# Power_Supply_Adapter_Schematic.net
KiCad netlist of a schematic drawn in EasyEDA
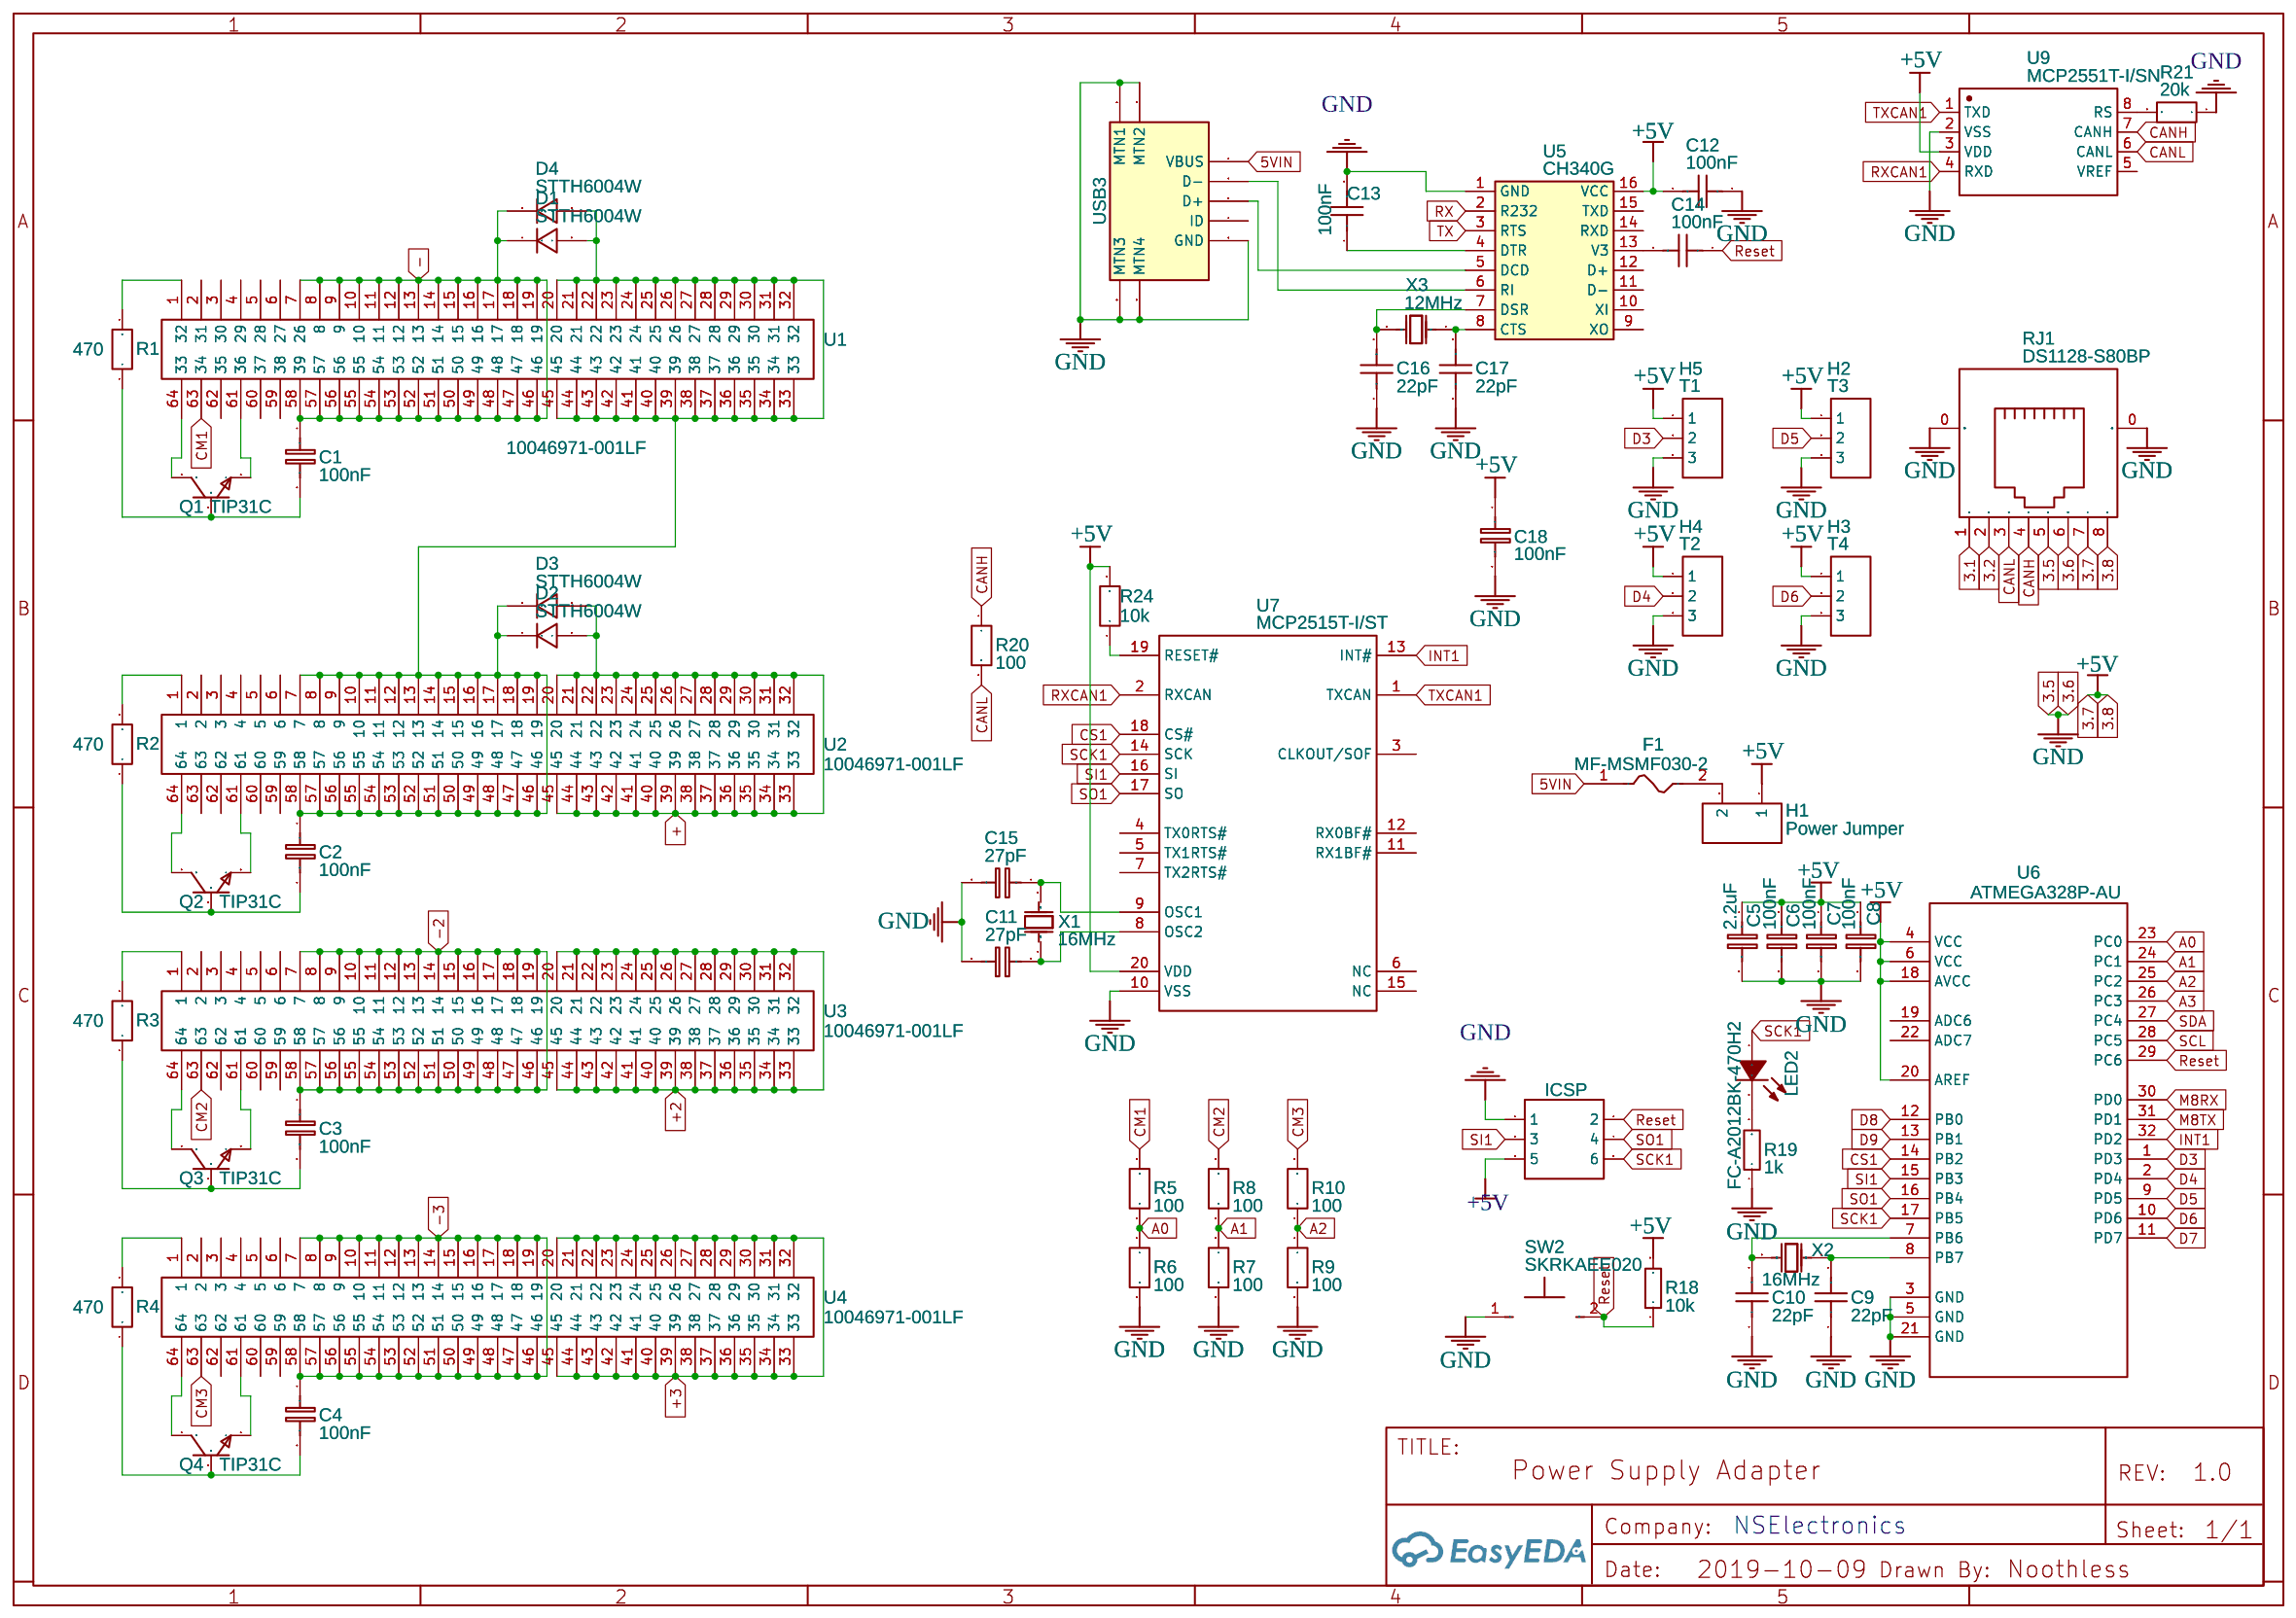
[diagram p0: schematic sheet]

(export (version "E")
  (design (tool "Eeschema 10.0.6"))
  (components
    (comp (ref "C1")
      (value "100nF")
      (fields
        (field (name "BOM_Manufacturer Part") "CL21B104KBCNNNC")
        (field (name "BOM_Supplier Part") "C1711")
      )
      (libsource (lib "") (part "Cap_0805_EU_2"))
    )
    (comp (ref "C2")
      (value "100nF")
      (fields
        (field (name "BOM_Manufacturer Part") "CL21B104KBCNNNC")
        (field (name "BOM_Supplier Part") "C1711")
      )
      (libsource (lib "") (part "Cap_0805_EU_2"))
    )
    (comp (ref "C3")
      (value "100nF")
      (fields
        (field (name "BOM_Manufacturer Part") "CL21B104KBCNNNC")
        (field (name "BOM_Supplier Part") "C1711")
      )
      (libsource (lib "") (part "Cap_0805_EU"))
    )
    (comp (ref "C4")
      (value "100nF")
      (fields
        (field (name "BOM_Manufacturer Part") "CL21B104KBCNNNC")
        (field (name "BOM_Supplier Part") "C1711")
      )
      (libsource (lib "") (part "Cap_0805_EU"))
    )
    (comp (ref "C5")
      (value "2.2uF")
      (fields
        (field (name "BOM_Manufacturer Part") "CL21B104KBCNNNC")
        (field (name "BOM_Supplier Part") "C1711")
      )
      (libsource (lib "") (part "Cap_1206_EU"))
    )
    (comp (ref "C6")
      (value "100nF")
      (fields
        (field (name "BOM_Manufacturer Part") "CL21B104KBCNNNC")
        (field (name "BOM_Supplier Part") "C1711")
      )
      (libsource (lib "") (part "Cap_1206_EU"))
    )
    (comp (ref "C7")
      (value "100nF")
      (fields
        (field (name "BOM_Manufacturer Part") "CL21B104KBCNNNC")
        (field (name "BOM_Supplier Part") "C1711")
      )
      (libsource (lib "") (part "Cap_1206_EU"))
    )
    (comp (ref "C8")
      (value "100nF")
      (fields
        (field (name "BOM_Manufacturer Part") "CL21B104KBCNNNC")
        (field (name "BOM_Supplier Part") "C1711")
      )
      (libsource (lib "") (part "Cap_1206_EU"))
    )
    (comp (ref "C9")
      (value "22pF")
      (fields
        (field (name "BOM_Manufacturer Part") "0805CG220J500NT")
        (field (name "BOM_Supplier Part") "C38143")
      )
      (libsource (lib "") (part "Cap_0805_US"))
    )
    (comp (ref "C10")
      (value "22pF")
      (fields
        (field (name "BOM_Manufacturer Part") "0805CG220J500NT")
        (field (name "BOM_Supplier Part") "C38143")
      )
      (libsource (lib "") (part "Cap_0805_US"))
    )
    (comp (ref "C11") (value "27pF") (libsource (lib "") (part "Cap_0805_EU_1")))
    (comp (ref "C12")
      (value "100nF")
      (fields
        (field (name "BOM_Manufacturer Part") "CL21B104KBCNNNC")
        (field (name "BOM_Supplier Part") "C1711")
      )
      (libsource (lib "") (part "Cap_0805_US_1"))
    )
    (comp (ref "C13")
      (value "100nF")
      (fields
        (field (name "BOM_Manufacturer Part") "CL21B104KBCNNNC")
        (field (name "BOM_Supplier Part") "C1711")
      )
      (libsource (lib "") (part "Cap_0805_US"))
    )
    (comp (ref "C14")
      (value "100nF")
      (fields (field (name "BOM_Manufacturer Part") "?"))
      (libsource (lib "") (part "Cap_0805_US_1"))
    )
    (comp (ref "C15") (value "27pF") (libsource (lib "") (part "Cap_0805_EU_1")))
    (comp (ref "C16")
      (value "22pF")
      (fields
        (field (name "BOM_Manufacturer Part") "0805CG220J500NT")
        (field (name "BOM_Supplier Part") "C38143")
      )
      (libsource (lib "") (part "Cap_0805_US"))
    )
    (comp (ref "C17")
      (value "22pF")
      (fields
        (field (name "BOM_Manufacturer Part") "0805CG220J500NT")
        (field (name "BOM_Supplier Part") "C38143")
      )
      (libsource (lib "") (part "Cap_0805_US"))
    )
    (comp (ref "C18") (value "100nF") (libsource (lib "") (part "Cap_0805_EU_3")))
    (comp (ref "D1")
      (value "STTH6004W")
      (fields (field (name "BOM_Supplier Part") "C169788"))
      (libsource (lib "") (part "Unknown_270_115"))
    )
    (comp (ref "D2")
      (value "STTH6004W")
      (fields (field (name "BOM_Supplier Part") "C169788"))
      (libsource (lib "") (part "Unknown_270_315"))
    )
    (comp (ref "D3")
      (value "STTH6004W")
      (fields (field (name "BOM_Supplier Part") "C169788"))
      (libsource (lib "") (part "Unknown_270_300"))
    )
    (comp (ref "D4")
      (value "STTH6004W")
      (fields (field (name "BOM_Supplier Part") "C169788"))
      (libsource (lib "") (part "Unknown_270_100"))
    )
    (comp (ref "F1")
      (value "MF-MSMF030-2")
      (fields (field (name "BOM_Supplier Part") "C12604"))
      (libsource (lib "") (part "Unknown_835_390"))
    )
    (comp (ref "H1")
      (value "Power Jumper")
      (fields (field (name "BOM_Manufacturer Part") "826629-2") (field (name "BOM_Supplier Part") "C86471"))
      (libsource (lib "") (part "Header-Male-2.54_1x2"))
    )
    (comp (ref "H2")
      (value "T3")
      (fields
        (field (name "BOM_Manufacturer Part") "Header2.54mm 1*3P")
        (field (name "BOM_Supplier Part") "C49257")
      )
      (libsource (lib "") (part "Header-Male-2.54_1x3"))
    )
    (comp (ref "H3")
      (value "T4")
      (fields
        (field (name "BOM_Manufacturer Part") "Header2.54mm 1*3P")
        (field (name "BOM_Supplier Part") "C49257")
      )
      (libsource (lib "") (part "Header-Male-2.54_1x3"))
    )
    (comp (ref "H4")
      (value "T2")
      (fields
        (field (name "BOM_Manufacturer Part") "Header2.54mm 1*3P")
        (field (name "BOM_Supplier Part") "C49257")
      )
      (libsource (lib "") (part "Header-Male-2.54_1x3"))
    )
    (comp (ref "H5")
      (value "T1")
      (fields
        (field (name "BOM_Manufacturer Part") "Header2.54mm 1*3P")
        (field (name "BOM_Supplier Part") "C49257")
      )
      (libsource (lib "") (part "Header-Male-2.54_1x3"))
    )
    (comp (ref "ICSP2")
      (value "ICSP")
      (fields
        (field (name "BOM_Manufacturer Part") "Header-Male-2.54_2x3")
        (field (name "BOM_Supplier Part") "C65114")
      )
      (libsource (lib "") (part "Unknown_785_570"))
    )
    (comp (ref "LED2")
      (value "FC-A2012BK-470H2")
      (fields (field (name "BOM_Supplier Part") "C84259"))
      (libsource (lib "") (part "Unknown_880_535"))
    )
    (comp (ref "Q1")
      (value "TIP31C")
      (fields (field (name "BOM_Supplier Part") "C13506"))
      (libsource (lib "") (part "Unknown_100_245"))
    )
    (comp (ref "Q2")
      (value "TIP31C")
      (fields (field (name "BOM_Supplier Part") "C13506"))
      (libsource (lib "") (part "Unknown_100_445"))
    )
    (comp (ref "Q3")
      (value "TIP31C")
      (fields (field (name "BOM_Supplier Part") "C13506"))
      (libsource (lib "") (part "Unknown_100_585"))
    )
    (comp (ref "Q4")
      (value "TIP31C")
      (fields (field (name "BOM_Supplier Part") "C13506"))
      (libsource (lib "") (part "Unknown_100_730"))
    )
    (comp (ref "R1")
      (value "470")
      (fields
        (field (name "BOM_Manufacturer Part") "0805W8J0471T5E")
        (field (name "BOM_Supplier Part") "C21266")
      )
      (libsource (lib "") (part "Res_0805(1/8W)_EU"))
    )
    (comp (ref "R2")
      (value "470")
      (fields
        (field (name "BOM_Manufacturer Part") "0805W8J0471T5E")
        (field (name "BOM_Supplier Part") "C21266")
      )
      (libsource (lib "") (part "Res_0805(1/8W)_EU"))
    )
    (comp (ref "R3")
      (value "470")
      (fields
        (field (name "BOM_Manufacturer Part") "0805W8J0471T5E")
        (field (name "BOM_Supplier Part") "C21266")
      )
      (libsource (lib "") (part "Res_0805(1/8W)_EU"))
    )
    (comp (ref "R4")
      (value "470")
      (fields
        (field (name "BOM_Manufacturer Part") "0805W8J0471T5E")
        (field (name "BOM_Supplier Part") "C21266")
      )
      (libsource (lib "") (part "Res_0805(1/8W)_EU"))
    )
    (comp (ref "R5") (value "100") (libsource (lib "") (part "Res_0805(1/8W)_EU")))
    (comp (ref "R6") (value "100") (libsource (lib "") (part "Res_0805(1/8W)_EU_1")))
    (comp (ref "R7") (value "100") (libsource (lib "") (part "Res_0805(1/8W)_EU_1")))
    (comp (ref "R8") (value "100") (libsource (lib "") (part "Res_0805(1/8W)_EU")))
    (comp (ref "R9") (value "100") (libsource (lib "") (part "Res_0805(1/8W)_EU_1")))
    (comp (ref "R10") (value "100") (libsource (lib "") (part "Res_0805(1/8W)_EU")))
    (comp (ref "R18")
      (value "10k")
      (fields
        (field (name "BOM_Manufacturer Part") "0805W8F1002T5E")
        (field (name "BOM_Supplier Part") "C17414")
      )
      (libsource (lib "") (part "Res_0805(1/8W)_EU_3"))
    )
    (comp (ref "R19")
      (value "1k")
      (fields
        (field (name "BOM_Manufacturer Part") "0805W8F1001T5E")
        (field (name "BOM_Supplier Part") "C17513")
      )
      (libsource (lib "") (part "Res_0805(1/8W)_EU_3"))
    )
    (comp (ref "R20") (value "100") (libsource (lib "") (part "Res_0805(1/8W)_EU_1")))
    (comp (ref "R21") (value "20k") (libsource (lib "") (part "Res_0805(1/8W)_EU_2")))
    (comp (ref "R24") (value "10k") (libsource (lib "") (part "Res_0805(1/8W)_EU")))
    (comp (ref "RJ1")
      (value "DS1128-S80BP")
      (fields (field (name "BOM_Supplier Part") "C86586"))
      (libsource (lib "") (part "Unknown_1025_225"))
    )
    (comp (ref "SW2")
      (value "SKRKAEE020")
      (fields (field (name "BOM_Supplier Part") "C115357"))
      (libsource (lib "") (part "Unknown_775_650"))
    )
    (comp (ref "U1")
      (value "10046971-001LF")
      (fields (field (name "BOM_Supplier Part") "609-2863-ND"))
      (libsource (lib "") (part "Unknown_75_185"))
    )
    (comp (ref "U2")
      (value "10046971-001LF")
      (fields (field (name "BOM_Supplier Part") "609-2863-ND"))
      (libsource (lib "") (part "Unknown_75_385"))
    )
    (comp (ref "U3")
      (value "10046971-001LF")
      (fields (field (name "BOM_Supplier Part") "609-2863-ND"))
      (libsource (lib "") (part "Unknown_75_525"))
    )
    (comp (ref "U4")
      (value "10046971-001LF")
      (fields (field (name "BOM_Supplier Part") "609-2863-ND"))
      (libsource (lib "") (part "Unknown_75_670"))
    )
    (comp (ref "U5")
      (value "CH340G")
      (fields (field (name "BOM_Supplier Part") "C14267"))
      (libsource (lib "") (part "Unknown_775_130"))
    )
    (comp (ref "U6")
      (value "ATMEGA328P-AU")
      (fields (field (name "BOM_Supplier Part") "C14877"))
      (libsource (lib "") (part "Unknown_1020_570"))
    )
    (comp (ref "U7")
      (value "MCP2515T-I/ST")
      (fields (field (name "BOM_Supplier Part") "C185941"))
      (libsource (lib "") (part "MCP2515T-I/ST"))
    )
    (comp (ref "U9")
      (value "MCP2551T-I/SN")
      (fields (field (name "BOM_Supplier Part") "C49558"))
      (libsource (lib "") (part "Unknown_1025_65"))
    )
    (comp (ref "USB3")
      (value "MINI 5PMotherboard Copper shell with column LCPVinyl")
      (fields (field (name "BOM_Supplier Part") "C46391"))
      (libsource (lib "") (part "Unknown_590_95"))
    )
    (comp (ref "X1")
      (value "16MHz")
      (fields
        (field (name "BOM_Manufacturer Part") "X49SD16MSD2SC")
        (field (name "BOM_Supplier Part") "C16212")
      )
      (libsource (lib "") (part "X49SD16MSD2SC_1"))
    )
    (comp (ref "X2")
      (value "16MHz")
      (fields
        (field (name "BOM_Manufacturer Part") "X49SD16MSD2SC")
        (field (name "BOM_Supplier Part") "C16212")
      )
      (libsource (lib "") (part "X49SD16MSD2SC"))
    )
    (comp (ref "X3")
      (value "12MHz")
      (fields
        (field (name "BOM_Manufacturer Part") "X49SD12MSD2SC")
        (field (name "BOM_Supplier Part") "C16369")
      )
      (libsource (lib "") (part "X49SD12MSD2SC"))
    )
  )
  (nets
    (net (code "1") (name "+") (class "Default")
      (node (ref "D2") (pin "2") (pinfunction "A_2") (pintype "unspecified"))
      (node (ref "D3") (pin "2") (pinfunction "A_2") (pintype "unspecified"))
      (node (ref "U2") (pin "20") (pinfunction "20_20") (pintype "unspecified"))
      (node (ref "U2") (pin "21") (pinfunction "21_21") (pintype "unspecified"))
      (node (ref "U2") (pin "22") (pinfunction "22_22") (pintype "unspecified"))
      (node (ref "U2") (pin "23") (pinfunction "23_23") (pintype "unspecified"))
      (node (ref "U2") (pin "24") (pinfunction "24_24") (pintype "unspecified"))
      (node (ref "U2") (pin "25") (pinfunction "25_25") (pintype "unspecified"))
      (node (ref "U2") (pin "26") (pinfunction "26_26") (pintype "unspecified"))
      (node (ref "U2") (pin "27") (pinfunction "27_27") (pintype "unspecified"))
      (node (ref "U2") (pin "28") (pinfunction "28_28") (pintype "unspecified"))
      (node (ref "U2") (pin "29") (pinfunction "29_29") (pintype "unspecified"))
      (node (ref "U2") (pin "30") (pinfunction "30_30") (pintype "unspecified"))
      (node (ref "U2") (pin "31") (pinfunction "31_31") (pintype "unspecified"))
      (node (ref "U2") (pin "32") (pinfunction "32_32") (pintype "unspecified"))
      (node (ref "U2") (pin "33") (pinfunction "33_33") (pintype "unspecified"))
      (node (ref "U2") (pin "34") (pinfunction "34_34") (pintype "unspecified"))
      (node (ref "U2") (pin "35") (pinfunction "35_35") (pintype "unspecified"))
      (node (ref "U2") (pin "36") (pinfunction "36_36") (pintype "unspecified"))
      (node (ref "U2") (pin "37") (pinfunction "37_37") (pintype "unspecified"))
      (node (ref "U2") (pin "38") (pinfunction "38_38") (pintype "unspecified"))
      (node (ref "U2") (pin "39") (pinfunction "39_39") (pintype "unspecified"))
      (node (ref "U2") (pin "40") (pinfunction "40_40") (pintype "unspecified"))
      (node (ref "U2") (pin "41") (pinfunction "41_41") (pintype "unspecified"))
      (node (ref "U2") (pin "42") (pinfunction "42_42") (pintype "unspecified"))
      (node (ref "U2") (pin "43") (pinfunction "43_43") (pintype "unspecified"))
      (node (ref "U2") (pin "44") (pinfunction "44_44") (pintype "unspecified"))
      (node (ref "U2") (pin "45") (pinfunction "45_45") (pintype "unspecified"))
    )
    (net (code "2") (name "+2") (class "Default")
      (node (ref "U3") (pin "20") (pinfunction "20_20") (pintype "unspecified"))
      (node (ref "U3") (pin "21") (pinfunction "21_21") (pintype "unspecified"))
      (node (ref "U3") (pin "22") (pinfunction "22_22") (pintype "unspecified"))
      (node (ref "U3") (pin "23") (pinfunction "23_23") (pintype "unspecified"))
      (node (ref "U3") (pin "24") (pinfunction "24_24") (pintype "unspecified"))
      (node (ref "U3") (pin "25") (pinfunction "25_25") (pintype "unspecified"))
      (node (ref "U3") (pin "26") (pinfunction "26_26") (pintype "unspecified"))
      (node (ref "U3") (pin "27") (pinfunction "27_27") (pintype "unspecified"))
      (node (ref "U3") (pin "28") (pinfunction "28_28") (pintype "unspecified"))
      (node (ref "U3") (pin "29") (pinfunction "29_29") (pintype "unspecified"))
      (node (ref "U3") (pin "30") (pinfunction "30_30") (pintype "unspecified"))
      (node (ref "U3") (pin "31") (pinfunction "31_31") (pintype "unspecified"))
      (node (ref "U3") (pin "32") (pinfunction "32_32") (pintype "unspecified"))
      (node (ref "U3") (pin "33") (pinfunction "33_33") (pintype "unspecified"))
      (node (ref "U3") (pin "34") (pinfunction "34_34") (pintype "unspecified"))
      (node (ref "U3") (pin "35") (pinfunction "35_35") (pintype "unspecified"))
      (node (ref "U3") (pin "36") (pinfunction "36_36") (pintype "unspecified"))
      (node (ref "U3") (pin "37") (pinfunction "37_37") (pintype "unspecified"))
      (node (ref "U3") (pin "38") (pinfunction "38_38") (pintype "unspecified"))
      (node (ref "U3") (pin "39") (pinfunction "39_39") (pintype "unspecified"))
      (node (ref "U3") (pin "40") (pinfunction "40_40") (pintype "unspecified"))
      (node (ref "U3") (pin "41") (pinfunction "41_41") (pintype "unspecified"))
      (node (ref "U3") (pin "42") (pinfunction "42_42") (pintype "unspecified"))
      (node (ref "U3") (pin "43") (pinfunction "43_43") (pintype "unspecified"))
      (node (ref "U3") (pin "44") (pinfunction "44_44") (pintype "unspecified"))
      (node (ref "U3") (pin "45") (pinfunction "45_45") (pintype "unspecified"))
    )
    (net (code "3") (name "+3") (class "Default")
      (node (ref "U4") (pin "20") (pinfunction "20_20") (pintype "unspecified"))
      (node (ref "U4") (pin "21") (pinfunction "21_21") (pintype "unspecified"))
      (node (ref "U4") (pin "22") (pinfunction "22_22") (pintype "unspecified"))
      (node (ref "U4") (pin "23") (pinfunction "23_23") (pintype "unspecified"))
      (node (ref "U4") (pin "24") (pinfunction "24_24") (pintype "unspecified"))
      (node (ref "U4") (pin "25") (pinfunction "25_25") (pintype "unspecified"))
      (node (ref "U4") (pin "26") (pinfunction "26_26") (pintype "unspecified"))
      (node (ref "U4") (pin "27") (pinfunction "27_27") (pintype "unspecified"))
      (node (ref "U4") (pin "28") (pinfunction "28_28") (pintype "unspecified"))
      (node (ref "U4") (pin "29") (pinfunction "29_29") (pintype "unspecified"))
      (node (ref "U4") (pin "30") (pinfunction "30_30") (pintype "unspecified"))
      (node (ref "U4") (pin "31") (pinfunction "31_31") (pintype "unspecified"))
      (node (ref "U4") (pin "32") (pinfunction "32_32") (pintype "unspecified"))
      (node (ref "U4") (pin "33") (pinfunction "33_33") (pintype "unspecified"))
      (node (ref "U4") (pin "34") (pinfunction "34_34") (pintype "unspecified"))
      (node (ref "U4") (pin "35") (pinfunction "35_35") (pintype "unspecified"))
      (node (ref "U4") (pin "36") (pinfunction "36_36") (pintype "unspecified"))
      (node (ref "U4") (pin "37") (pinfunction "37_37") (pintype "unspecified"))
      (node (ref "U4") (pin "38") (pinfunction "38_38") (pintype "unspecified"))
      (node (ref "U4") (pin "39") (pinfunction "39_39") (pintype "unspecified"))
      (node (ref "U4") (pin "40") (pinfunction "40_40") (pintype "unspecified"))
      (node (ref "U4") (pin "41") (pinfunction "41_41") (pintype "unspecified"))
      (node (ref "U4") (pin "42") (pinfunction "42_42") (pintype "unspecified"))
      (node (ref "U4") (pin "43") (pinfunction "43_43") (pintype "unspecified"))
      (node (ref "U4") (pin "44") (pinfunction "44_44") (pintype "unspecified"))
      (node (ref "U4") (pin "45") (pinfunction "45_45") (pintype "unspecified"))
    )
    (net (code "4") (name "-") (class "Default")
      (node (ref "C1") (pin "1") (pinfunction "1_1") (pintype "unspecified"))
      (node (ref "D1") (pin "1") (pinfunction "K_1") (pintype "unspecified"))
      (node (ref "D4") (pin "1") (pinfunction "K_1") (pintype "unspecified"))
      (node (ref "U1") (pin "10") (pinfunction "10_10") (pintype "unspecified"))
      (node (ref "U1") (pin "11") (pinfunction "11_11") (pintype "unspecified"))
      (node (ref "U1") (pin "12") (pinfunction "12_12") (pintype "unspecified"))
      (node (ref "U1") (pin "13") (pinfunction "13_13") (pintype "unspecified"))
      (node (ref "U1") (pin "14") (pinfunction "14_14") (pintype "unspecified"))
      (node (ref "U1") (pin "15") (pinfunction "15_15") (pintype "unspecified"))
      (node (ref "U1") (pin "16") (pinfunction "16_16") (pintype "unspecified"))
      (node (ref "U1") (pin "17") (pinfunction "17_17") (pintype "unspecified"))
      (node (ref "U1") (pin "18") (pinfunction "18_18") (pintype "unspecified"))
      (node (ref "U1") (pin "19") (pinfunction "19_19") (pintype "unspecified"))
      (node (ref "U1") (pin "46") (pinfunction "46_46") (pintype "unspecified"))
      (node (ref "U1") (pin "47") (pinfunction "47_47") (pintype "unspecified"))
      (node (ref "U1") (pin "48") (pinfunction "48_48") (pintype "unspecified"))
      (node (ref "U1") (pin "49") (pinfunction "49_49") (pintype "unspecified"))
      (node (ref "U1") (pin "50") (pinfunction "50_50") (pintype "unspecified"))
      (node (ref "U1") (pin "51") (pinfunction "51_51") (pintype "unspecified"))
      (node (ref "U1") (pin "52") (pinfunction "52_52") (pintype "unspecified"))
      (node (ref "U1") (pin "53") (pinfunction "53_53") (pintype "unspecified"))
      (node (ref "U1") (pin "54") (pinfunction "54_54") (pintype "unspecified"))
      (node (ref "U1") (pin "55") (pinfunction "55_55") (pintype "unspecified"))
      (node (ref "U1") (pin "56") (pinfunction "56_56") (pintype "unspecified"))
      (node (ref "U1") (pin "57") (pinfunction "57_57") (pintype "unspecified"))
      (node (ref "U1") (pin "58") (pinfunction "39_58") (pintype "unspecified"))
      (node (ref "U1") (pin "7") (pinfunction "26_7") (pintype "unspecified"))
      (node (ref "U1") (pin "8") (pinfunction "8_8") (pintype "unspecified"))
      (node (ref "U1") (pin "9") (pinfunction "9_9") (pintype "unspecified"))
    )
    (net (code "5") (name "-2") (class "Default")
      (node (ref "C3") (pin "1") (pinfunction "1_1") (pintype "unspecified"))
      (node (ref "U3") (pin "10") (pinfunction "10_10") (pintype "unspecified"))
      (node (ref "U3") (pin "11") (pinfunction "11_11") (pintype "unspecified"))
      (node (ref "U3") (pin "12") (pinfunction "12_12") (pintype "unspecified"))
      (node (ref "U3") (pin "13") (pinfunction "13_13") (pintype "unspecified"))
      (node (ref "U3") (pin "14") (pinfunction "14_14") (pintype "unspecified"))
      (node (ref "U3") (pin "15") (pinfunction "15_15") (pintype "unspecified"))
      (node (ref "U3") (pin "16") (pinfunction "16_16") (pintype "unspecified"))
      (node (ref "U3") (pin "17") (pinfunction "17_17") (pintype "unspecified"))
      (node (ref "U3") (pin "18") (pinfunction "18_18") (pintype "unspecified"))
      (node (ref "U3") (pin "19") (pinfunction "19_19") (pintype "unspecified"))
      (node (ref "U3") (pin "46") (pinfunction "46_46") (pintype "unspecified"))
      (node (ref "U3") (pin "47") (pinfunction "47_47") (pintype "unspecified"))
      (node (ref "U3") (pin "48") (pinfunction "48_48") (pintype "unspecified"))
      (node (ref "U3") (pin "49") (pinfunction "49_49") (pintype "unspecified"))
      (node (ref "U3") (pin "50") (pinfunction "50_50") (pintype "unspecified"))
      (node (ref "U3") (pin "51") (pinfunction "51_51") (pintype "unspecified"))
      (node (ref "U3") (pin "52") (pinfunction "52_52") (pintype "unspecified"))
      (node (ref "U3") (pin "53") (pinfunction "53_53") (pintype "unspecified"))
      (node (ref "U3") (pin "54") (pinfunction "54_54") (pintype "unspecified"))
      (node (ref "U3") (pin "55") (pinfunction "55_55") (pintype "unspecified"))
      (node (ref "U3") (pin "56") (pinfunction "56_56") (pintype "unspecified"))
      (node (ref "U3") (pin "57") (pinfunction "57_57") (pintype "unspecified"))
      (node (ref "U3") (pin "58") (pinfunction "58_58") (pintype "unspecified"))
      (node (ref "U3") (pin "7") (pinfunction "7_7") (pintype "unspecified"))
      (node (ref "U3") (pin "8") (pinfunction "8_8") (pintype "unspecified"))
      (node (ref "U3") (pin "9") (pinfunction "9_9") (pintype "unspecified"))
    )
    (net (code "6") (name "-3") (class "Default")
      (node (ref "C4") (pin "1") (pinfunction "1_1") (pintype "unspecified"))
      (node (ref "U4") (pin "10") (pinfunction "10_10") (pintype "unspecified"))
      (node (ref "U4") (pin "11") (pinfunction "11_11") (pintype "unspecified"))
      (node (ref "U4") (pin "12") (pinfunction "12_12") (pintype "unspecified"))
      (node (ref "U4") (pin "13") (pinfunction "13_13") (pintype "unspecified"))
      (node (ref "U4") (pin "14") (pinfunction "14_14") (pintype "unspecified"))
      (node (ref "U4") (pin "15") (pinfunction "15_15") (pintype "unspecified"))
      (node (ref "U4") (pin "16") (pinfunction "16_16") (pintype "unspecified"))
      (node (ref "U4") (pin "17") (pinfunction "17_17") (pintype "unspecified"))
      (node (ref "U4") (pin "18") (pinfunction "18_18") (pintype "unspecified"))
      (node (ref "U4") (pin "19") (pinfunction "19_19") (pintype "unspecified"))
      (node (ref "U4") (pin "46") (pinfunction "46_46") (pintype "unspecified"))
      (node (ref "U4") (pin "47") (pinfunction "47_47") (pintype "unspecified"))
      (node (ref "U4") (pin "48") (pinfunction "48_48") (pintype "unspecified"))
      (node (ref "U4") (pin "49") (pinfunction "49_49") (pintype "unspecified"))
      (node (ref "U4") (pin "50") (pinfunction "50_50") (pintype "unspecified"))
      (node (ref "U4") (pin "51") (pinfunction "51_51") (pintype "unspecified"))
      (node (ref "U4") (pin "52") (pinfunction "52_52") (pintype "unspecified"))
      (node (ref "U4") (pin "53") (pinfunction "53_53") (pintype "unspecified"))
      (node (ref "U4") (pin "54") (pinfunction "54_54") (pintype "unspecified"))
      (node (ref "U4") (pin "55") (pinfunction "55_55") (pintype "unspecified"))
      (node (ref "U4") (pin "56") (pinfunction "56_56") (pintype "unspecified"))
      (node (ref "U4") (pin "57") (pinfunction "57_57") (pintype "unspecified"))
      (node (ref "U4") (pin "58") (pinfunction "58_58") (pintype "unspecified"))
      (node (ref "U4") (pin "7") (pinfunction "7_7") (pintype "unspecified"))
      (node (ref "U4") (pin "8") (pinfunction "8_8") (pintype "unspecified"))
      (node (ref "U4") (pin "9") (pinfunction "9_9") (pintype "unspecified"))
    )
    (net (code "7") (name "3.1") (class "Default")
      (node (ref "RJ1") (pin "1") (pinfunction "1_1") (pintype "unspecified"))
    )
    (net (code "8") (name "3.2") (class "Default")
      (node (ref "RJ1") (pin "2") (pinfunction "2_2") (pintype "unspecified"))
    )
    (net (code "9") (name "3.5") (class "Default")
      (node (ref "C10") (pin "1") (pinfunction "1_1") (pintype "unspecified"))
      (node (ref "C11") (pin "2") (pinfunction "2_2") (pintype "unspecified"))
      (node (ref "C12") (pin "1") (pinfunction "1_1") (pintype "unspecified"))
      (node (ref "C13") (pin "2") (pinfunction "2_2") (pintype "unspecified"))
      (node (ref "C15") (pin "2") (pinfunction "2_2") (pintype "unspecified"))
      (node (ref "C16") (pin "1") (pinfunction "1_1") (pintype "unspecified"))
      (node (ref "C17") (pin "1") (pinfunction "1_1") (pintype "unspecified"))
      (node (ref "C18") (pin "2") (pinfunction "2_2") (pintype "unspecified"))
      (node (ref "C5") (pin "2") (pinfunction "2_2") (pintype "unspecified"))
      (node (ref "C6") (pin "2") (pinfunction "2_2") (pintype "unspecified"))
      (node (ref "C7") (pin "2") (pinfunction "2_2") (pintype "unspecified"))
      (node (ref "C8") (pin "2") (pinfunction "2_2") (pintype "unspecified"))
      (node (ref "C9") (pin "1") (pinfunction "1_1") (pintype "unspecified"))
      (node (ref "H2") (pin "3") (pinfunction "3_3") (pintype "input"))
      (node (ref "H3") (pin "3") (pinfunction "3_3") (pintype "input"))
      (node (ref "H4") (pin "3") (pinfunction "3_3") (pintype "input"))
      (node (ref "H5") (pin "3") (pinfunction "3_3") (pintype "input"))
      (node (ref "ICSP2") (pin "1") (pinfunction "1_1") (pintype "input"))
      (node (ref "R19") (pin "1") (pinfunction "1_1") (pintype "unspecified"))
      (node (ref "R21") (pin "1") (pinfunction "1_1") (pintype "unspecified"))
      (node (ref "R6") (pin "2") (pinfunction "2_2") (pintype "unspecified"))
      (node (ref "R7") (pin "2") (pinfunction "2_2") (pintype "unspecified"))
      (node (ref "R9") (pin "2") (pinfunction "2_2") (pintype "unspecified"))
      (node (ref "RJ1") (pin "0") (pinfunction "SHIELD_0") (pintype "unspecified"))
      (node (ref "RJ1") (pin "5") (pinfunction "5_5") (pintype "unspecified"))
      (node (ref "RJ1") (pin "6") (pinfunction "6_6") (pintype "unspecified"))
      (node (ref "SW2") (pin "1") (pinfunction "1_1") (pintype "input"))
      (node (ref "U5") (pin "1") (pinfunction "GND_1") (pintype "unspecified"))
      (node (ref "U6") (pin "21") (pinfunction "GND_21") (pintype "unspecified"))
      (node (ref "U6") (pin "3") (pinfunction "GND_3") (pintype "unspecified"))
      (node (ref "U6") (pin "5") (pinfunction "GND_5") (pintype "unspecified"))
      (node (ref "U7") (pin "10") (pinfunction "VSS_10") (pintype "passive"))
      (node (ref "U9") (pin "2") (pinfunction "VSS_2") (pintype "unspecified"))
      (node (ref "USB3") (pin "0") (pinfunction "MTN4_0") (pintype "input"))
      (node (ref "USB3") (pin "5") (pinfunction "GND_5") (pintype "input"))
    )
    (net (code "10") (name "3.7") (class "Default")
      (node (ref "C12") (pin "2") (pinfunction "2_2") (pintype "unspecified"))
      (node (ref "C18") (pin "1") (pinfunction "1_1") (pintype "unspecified"))
      (node (ref "C5") (pin "1") (pinfunction "1_1") (pintype "unspecified"))
      (node (ref "C6") (pin "1") (pinfunction "1_1") (pintype "unspecified"))
      (node (ref "C7") (pin "1") (pinfunction "1_1") (pintype "unspecified"))
      (node (ref "C8") (pin "1") (pinfunction "1_1") (pintype "unspecified"))
      (node (ref "H1") (pin "1") (pinfunction "1_1") (pintype "unspecified"))
      (node (ref "H2") (pin "1") (pinfunction "1_1") (pintype "input"))
      (node (ref "H3") (pin "1") (pinfunction "1_1") (pintype "input"))
      (node (ref "H4") (pin "1") (pinfunction "1_1") (pintype "input"))
      (node (ref "H5") (pin "1") (pinfunction "1_1") (pintype "input"))
      (node (ref "ICSP2") (pin "5") (pinfunction "5_5") (pintype "input"))
      (node (ref "R18") (pin "2") (pinfunction "2_2") (pintype "unspecified"))
      (node (ref "R24") (pin "2") (pinfunction "2_2") (pintype "unspecified"))
      (node (ref "RJ1") (pin "7") (pinfunction "7_7") (pintype "unspecified"))
      (node (ref "RJ1") (pin "8") (pinfunction "8_8") (pintype "unspecified"))
      (node (ref "U5") (pin "16") (pinfunction "VCC_16") (pintype "unspecified"))
      (node (ref "U6") (pin "18") (pinfunction "AVCC_18") (pintype "passive"))
      (node (ref "U6") (pin "20") (pinfunction "AREF_20") (pintype "input"))
      (node (ref "U6") (pin "4") (pinfunction "VCC_4") (pintype "passive"))
      (node (ref "U6") (pin "6") (pinfunction "VCC_6") (pintype "passive"))
      (node (ref "U7") (pin "20") (pinfunction "VDD_20") (pintype "passive"))
      (node (ref "U9") (pin "3") (pinfunction "VDD_3") (pintype "unspecified"))
    )
    (net (code "11") (name "5VIN") (class "Default")
      (node (ref "F1") (pin "1") (pinfunction "1_1") (pintype "unspecified"))
      (node (ref "USB3") (pin "1") (pinfunction "VBUS_1") (pintype "input"))
    )
    (net (code "12") (name "A0") (class "Default")
      (node (ref "R5") (pin "1") (pinfunction "1_1") (pintype "unspecified"))
      (node (ref "R6") (pin "1") (pinfunction "1_1") (pintype "unspecified"))
      (node (ref "U6") (pin "23") (pinfunction "PC0_23") (pintype "unspecified"))
    )
    (net (code "13") (name "A1") (class "Default")
      (node (ref "R7") (pin "1") (pinfunction "1_1") (pintype "unspecified"))
      (node (ref "R8") (pin "1") (pinfunction "1_1") (pintype "unspecified"))
      (node (ref "U6") (pin "24") (pinfunction "PC1_24") (pintype "unspecified"))
    )
    (net (code "14") (name "A2") (class "Default")
      (node (ref "R10") (pin "1") (pinfunction "1_1") (pintype "unspecified"))
      (node (ref "R9") (pin "1") (pinfunction "1_1") (pintype "unspecified"))
      (node (ref "U6") (pin "25") (pinfunction "PC2_25") (pintype "unspecified"))
    )
    (net (code "15") (name "A3") (class "Default")
      (node (ref "U6") (pin "26") (pinfunction "PC3_26") (pintype "unspecified"))
    )
    (net (code "16") (name "CANH") (class "Default")
      (node (ref "R20") (pin "1") (pinfunction "1_1") (pintype "unspecified"))
      (node (ref "RJ1") (pin "4") (pinfunction "4_4") (pintype "unspecified"))
      (node (ref "U9") (pin "7") (pinfunction "CANH_7") (pintype "unspecified"))
    )
    (net (code "17") (name "CANL") (class "Default")
      (node (ref "R20") (pin "2") (pinfunction "2_2") (pintype "unspecified"))
      (node (ref "RJ1") (pin "3") (pinfunction "3_3") (pintype "unspecified"))
      (node (ref "U9") (pin "6") (pinfunction "CANL_6") (pintype "unspecified"))
    )
    (net (code "18") (name "CM1") (class "Default")
      (node (ref "R5") (pin "2") (pinfunction "2_2") (pintype "unspecified"))
      (node (ref "U1") (pin "63") (pinfunction "34_63") (pintype "unspecified"))
    )
    (net (code "19") (name "CM2") (class "Default")
      (node (ref "R8") (pin "2") (pinfunction "2_2") (pintype "unspecified"))
      (node (ref "U3") (pin "63") (pinfunction "63_63") (pintype "unspecified"))
    )
    (net (code "20") (name "CM3") (class "Default")
      (node (ref "R10") (pin "2") (pinfunction "2_2") (pintype "unspecified"))
      (node (ref "U4") (pin "63") (pinfunction "63_63") (pintype "unspecified"))
    )
    (net (code "21") (name "CS1") (class "Default")
      (node (ref "U6") (pin "14") (pinfunction "PB2_14") (pintype "unspecified"))
      (node (ref "U7") (pin "18") (pinfunction "CS#_18") (pintype "unspecified"))
    )
    (net (code "22") (name "D3") (class "Default")
      (node (ref "H5") (pin "2") (pinfunction "2_2") (pintype "input"))
      (node (ref "U6") (pin "1") (pinfunction "PD3_1") (pintype "unspecified"))
    )
    (net (code "23") (name "D4") (class "Default")
      (node (ref "H4") (pin "2") (pinfunction "2_2") (pintype "input"))
      (node (ref "U6") (pin "2") (pinfunction "PD4_2") (pintype "unspecified"))
    )
    (net (code "24") (name "D5") (class "Default")
      (node (ref "H2") (pin "2") (pinfunction "2_2") (pintype "input"))
      (node (ref "U6") (pin "9") (pinfunction "PD5_9") (pintype "unspecified"))
    )
    (net (code "25") (name "D6") (class "Default")
      (node (ref "H3") (pin "2") (pinfunction "2_2") (pintype "input"))
      (node (ref "U6") (pin "10") (pinfunction "PD6_10") (pintype "unspecified"))
    )
    (net (code "26") (name "D7") (class "Default")
      (node (ref "U6") (pin "11") (pinfunction "PD7_11") (pintype "unspecified"))
    )
    (net (code "27") (name "D8") (class "Default")
      (node (ref "U6") (pin "12") (pinfunction "PB0_12") (pintype "unspecified"))
    )
    (net (code "28") (name "D9") (class "Default")
      (node (ref "U6") (pin "13") (pinfunction "PB1_13") (pintype "unspecified"))
    )
    (net (code "29") (name "INT1") (class "Default")
      (node (ref "U6") (pin "32") (pinfunction "PD2_32") (pintype "unspecified"))
      (node (ref "U7") (pin "13") (pinfunction "INT#_13") (pintype "output"))
    )
    (net (code "30") (name "M8RX") (class "Default")
      (node (ref "U6") (pin "30") (pinfunction "PD0_30") (pintype "unspecified"))
    )
    (net (code "31") (name "M8TX") (class "Default")
      (node (ref "U6") (pin "31") (pinfunction "PD1_31") (pintype "unspecified"))
    )
    (net (code "32") (name "Net-(D1-A)") (class "Default")
      (node (ref "C2") (pin "1") (pinfunction "1_1") (pintype "unspecified"))
      (node (ref "D1") (pin "2") (pinfunction "A_2") (pintype "unspecified"))
      (node (ref "D2") (pin "1") (pinfunction "K_1") (pintype "unspecified"))
      (node (ref "D3") (pin "1") (pinfunction "K_1") (pintype "unspecified"))
      (node (ref "D4") (pin "2") (pinfunction "A_2") (pintype "unspecified"))
      (node (ref "U1") (pin "20") (pinfunction "20_20") (pintype "unspecified"))
      (node (ref "U1") (pin "21") (pinfunction "21_21") (pintype "unspecified"))
      (node (ref "U1") (pin "22") (pinfunction "22_22") (pintype "unspecified"))
      (node (ref "U1") (pin "23") (pinfunction "23_23") (pintype "unspecified"))
      (node (ref "U1") (pin "24") (pinfunction "24_24") (pintype "unspecified"))
      (node (ref "U1") (pin "25") (pinfunction "25_25") (pintype "unspecified"))
      (node (ref "U1") (pin "26") (pinfunction "26_26") (pintype "unspecified"))
      (node (ref "U1") (pin "27") (pinfunction "27_27") (pintype "unspecified"))
      (node (ref "U1") (pin "28") (pinfunction "28_28") (pintype "unspecified"))
      (node (ref "U1") (pin "29") (pinfunction "29_29") (pintype "unspecified"))
      (node (ref "U1") (pin "30") (pinfunction "30_30") (pintype "unspecified"))
      (node (ref "U1") (pin "31") (pinfunction "31_31") (pintype "unspecified"))
      (node (ref "U1") (pin "32") (pinfunction "32_32") (pintype "unspecified"))
      (node (ref "U1") (pin "33") (pinfunction "33_33") (pintype "unspecified"))
      (node (ref "U1") (pin "34") (pinfunction "34_34") (pintype "unspecified"))
      (node (ref "U1") (pin "35") (pinfunction "35_35") (pintype "unspecified"))
      (node (ref "U1") (pin "36") (pinfunction "36_36") (pintype "unspecified"))
      (node (ref "U1") (pin "37") (pinfunction "37_37") (pintype "unspecified"))
      (node (ref "U1") (pin "38") (pinfunction "38_38") (pintype "unspecified"))
      (node (ref "U1") (pin "39") (pinfunction "39_39") (pintype "unspecified"))
      (node (ref "U1") (pin "40") (pinfunction "40_40") (pintype "unspecified"))
      (node (ref "U1") (pin "41") (pinfunction "41_41") (pintype "unspecified"))
      (node (ref "U1") (pin "42") (pinfunction "42_42") (pintype "unspecified"))
      (node (ref "U1") (pin "43") (pinfunction "43_43") (pintype "unspecified"))
      (node (ref "U1") (pin "44") (pinfunction "44_44") (pintype "unspecified"))
      (node (ref "U1") (pin "45") (pinfunction "45_45") (pintype "unspecified"))
      (node (ref "U2") (pin "10") (pinfunction "10_10") (pintype "unspecified"))
      (node (ref "U2") (pin "11") (pinfunction "11_11") (pintype "unspecified"))
      (node (ref "U2") (pin "12") (pinfunction "12_12") (pintype "unspecified"))
      (node (ref "U2") (pin "13") (pinfunction "13_13") (pintype "unspecified"))
      (node (ref "U2") (pin "14") (pinfunction "14_14") (pintype "unspecified"))
      (node (ref "U2") (pin "15") (pinfunction "15_15") (pintype "unspecified"))
      (node (ref "U2") (pin "16") (pinfunction "16_16") (pintype "unspecified"))
      (node (ref "U2") (pin "17") (pinfunction "17_17") (pintype "unspecified"))
      (node (ref "U2") (pin "18") (pinfunction "18_18") (pintype "unspecified"))
      (node (ref "U2") (pin "19") (pinfunction "19_19") (pintype "unspecified"))
      (node (ref "U2") (pin "46") (pinfunction "46_46") (pintype "unspecified"))
      (node (ref "U2") (pin "47") (pinfunction "47_47") (pintype "unspecified"))
      (node (ref "U2") (pin "48") (pinfunction "48_48") (pintype "unspecified"))
      (node (ref "U2") (pin "49") (pinfunction "49_49") (pintype "unspecified"))
      (node (ref "U2") (pin "50") (pinfunction "50_50") (pintype "unspecified"))
      (node (ref "U2") (pin "51") (pinfunction "51_51") (pintype "unspecified"))
      (node (ref "U2") (pin "52") (pinfunction "52_52") (pintype "unspecified"))
      (node (ref "U2") (pin "53") (pinfunction "53_53") (pintype "unspecified"))
      (node (ref "U2") (pin "54") (pinfunction "54_54") (pintype "unspecified"))
      (node (ref "U2") (pin "55") (pinfunction "55_55") (pintype "unspecified"))
      (node (ref "U2") (pin "56") (pinfunction "56_56") (pintype "unspecified"))
      (node (ref "U2") (pin "57") (pinfunction "57_57") (pintype "unspecified"))
      (node (ref "U2") (pin "58") (pinfunction "58_58") (pintype "unspecified"))
      (node (ref "U2") (pin "7") (pinfunction "7_7") (pintype "unspecified"))
      (node (ref "U2") (pin "8") (pinfunction "8_8") (pintype "unspecified"))
      (node (ref "U2") (pin "9") (pinfunction "9_9") (pintype "unspecified"))
    )
    (net (code "33") (name "Net-(F1-Pad2)") (class "Default")
      (node (ref "F1") (pin "2") (pinfunction "2_2") (pintype "unspecified"))
      (node (ref "H1") (pin "2") (pinfunction "2_2") (pintype "unspecified"))
    )
    (net (code "34") (name "Net-(LED2-K)") (class "Default")
      (node (ref "LED2") (pin "2") (pinfunction "K_2") (pintype "unspecified"))
      (node (ref "R19") (pin "2") (pinfunction "2_2") (pintype "unspecified"))
    )
    (net (code "35") (name "Net-(Q1-B)") (class "Default")
      (node (ref "C1") (pin "2") (pinfunction "2_2") (pintype "unspecified"))
      (node (ref "Q1") (pin "1") (pinfunction "B_1") (pintype "unspecified"))
      (node (ref "R1") (pin "1") (pinfunction "1_1") (pintype "unspecified"))
    )
    (net (code "36") (name "Net-(Q1-C)") (class "Default")
      (node (ref "Q1") (pin "2") (pinfunction "C_2") (pintype "unspecified"))
      (node (ref "U1") (pin "64") (pinfunction "33_64") (pintype "unspecified"))
    )
    (net (code "37") (name "Net-(Q1-E)") (class "Default")
      (node (ref "Q1") (pin "3") (pinfunction "E_3") (pintype "unspecified"))
      (node (ref "U1") (pin "61") (pinfunction "36_61") (pintype "unspecified"))
    )
    (net (code "38") (name "Net-(Q2-B)") (class "Default")
      (node (ref "C2") (pin "2") (pinfunction "2_2") (pintype "unspecified"))
      (node (ref "Q2") (pin "1") (pinfunction "B_1") (pintype "unspecified"))
      (node (ref "R2") (pin "1") (pinfunction "1_1") (pintype "unspecified"))
    )
    (net (code "39") (name "Net-(Q2-C)") (class "Default")
      (node (ref "Q2") (pin "2") (pinfunction "C_2") (pintype "unspecified"))
      (node (ref "U2") (pin "64") (pinfunction "64_64") (pintype "unspecified"))
    )
    (net (code "40") (name "Net-(Q2-E)") (class "Default")
      (node (ref "Q2") (pin "3") (pinfunction "E_3") (pintype "unspecified"))
      (node (ref "U2") (pin "61") (pinfunction "61_61") (pintype "unspecified"))
    )
    (net (code "41") (name "Net-(Q3-B)") (class "Default")
      (node (ref "C3") (pin "2") (pinfunction "2_2") (pintype "unspecified"))
      (node (ref "Q3") (pin "1") (pinfunction "B_1") (pintype "unspecified"))
      (node (ref "R3") (pin "1") (pinfunction "1_1") (pintype "unspecified"))
    )
    (net (code "42") (name "Net-(Q3-C)") (class "Default")
      (node (ref "Q3") (pin "2") (pinfunction "C_2") (pintype "unspecified"))
      (node (ref "U3") (pin "64") (pinfunction "64_64") (pintype "unspecified"))
    )
    (net (code "43") (name "Net-(Q3-E)") (class "Default")
      (node (ref "Q3") (pin "3") (pinfunction "E_3") (pintype "unspecified"))
      (node (ref "U3") (pin "61") (pinfunction "61_61") (pintype "unspecified"))
    )
    (net (code "44") (name "Net-(Q4-B)") (class "Default")
      (node (ref "C4") (pin "2") (pinfunction "2_2") (pintype "unspecified"))
      (node (ref "Q4") (pin "1") (pinfunction "B_1") (pintype "unspecified"))
      (node (ref "R4") (pin "1") (pinfunction "1_1") (pintype "unspecified"))
    )
    (net (code "45") (name "Net-(Q4-C)") (class "Default")
      (node (ref "Q4") (pin "2") (pinfunction "C_2") (pintype "unspecified"))
      (node (ref "U4") (pin "64") (pinfunction "64_64") (pintype "unspecified"))
    )
    (net (code "46") (name "Net-(Q4-E)") (class "Default")
      (node (ref "Q4") (pin "3") (pinfunction "E_3") (pintype "unspecified"))
      (node (ref "U4") (pin "61") (pinfunction "61_61") (pintype "unspecified"))
    )
    (net (code "47") (name "Net-(R1-Pad2)") (class "Default")
      (node (ref "R1") (pin "2") (pinfunction "2_2") (pintype "unspecified"))
      (node (ref "U1") (pin "1") (pinfunction "32_1") (pintype "unspecified"))
    )
    (net (code "48") (name "Net-(R2-Pad2)") (class "Default")
      (node (ref "R2") (pin "2") (pinfunction "2_2") (pintype "unspecified"))
      (node (ref "U2") (pin "1") (pinfunction "1_1") (pintype "unspecified"))
    )
    (net (code "49") (name "Net-(R3-Pad2)") (class "Default")
      (node (ref "R3") (pin "2") (pinfunction "2_2") (pintype "unspecified"))
      (node (ref "U3") (pin "1") (pinfunction "1_1") (pintype "unspecified"))
    )
    (net (code "50") (name "Net-(R4-Pad2)") (class "Default")
      (node (ref "R4") (pin "2") (pinfunction "2_2") (pintype "unspecified"))
      (node (ref "U4") (pin "1") (pinfunction "1_1") (pintype "unspecified"))
    )
    (net (code "51") (name "Net-(U5-CTS)") (class "Default")
      (node (ref "C17") (pin "2") (pinfunction "2_2") (pintype "unspecified"))
      (node (ref "U5") (pin "8") (pinfunction "CTS_8") (pintype "unspecified"))
      (node (ref "X3") (pin "1") (pinfunction "OSC1_1") (pintype "input"))
    )
    (net (code "52") (name "Net-(U5-DCD)") (class "Default")
      (node (ref "U5") (pin "5") (pinfunction "DCD_5") (pintype "unspecified"))
      (node (ref "USB3") (pin "3") (pinfunction "D+_3") (pintype "input"))
    )
    (net (code "53") (name "Net-(U5-DSR)") (class "Default")
      (node (ref "C16") (pin "2") (pinfunction "2_2") (pintype "unspecified"))
      (node (ref "U5") (pin "7") (pinfunction "DSR_7") (pintype "unspecified"))
      (node (ref "X3") (pin "2") (pinfunction "OSC2_2") (pintype "input"))
    )
    (net (code "54") (name "Net-(U5-DTR)") (class "Default")
      (node (ref "C13") (pin "1") (pinfunction "1_1") (pintype "unspecified"))
      (node (ref "U5") (pin "4") (pinfunction "DTR_4") (pintype "unspecified"))
    )
    (net (code "55") (name "Net-(U5-RI)") (class "Default")
      (node (ref "U5") (pin "6") (pinfunction "RI_6") (pintype "unspecified"))
      (node (ref "USB3") (pin "2") (pinfunction "D-_2") (pintype "input"))
    )
    (net (code "56") (name "Net-(U5-V3)") (class "Default")
      (node (ref "C14") (pin "2") (pinfunction "2_2") (pintype "unspecified"))
      (node (ref "U5") (pin "13") (pinfunction "V3_13") (pintype "unspecified"))
    )
    (net (code "57") (name "Net-(U6-PB6)") (class "Default")
      (node (ref "C10") (pin "2") (pinfunction "2_2") (pintype "unspecified"))
      (node (ref "U6") (pin "7") (pinfunction "PB6_7") (pintype "unspecified"))
      (node (ref "X2") (pin "2") (pinfunction "OSC2_2") (pintype "input"))
    )
    (net (code "58") (name "Net-(U6-PB7)") (class "Default")
      (node (ref "C9") (pin "2") (pinfunction "2_2") (pintype "unspecified"))
      (node (ref "U6") (pin "8") (pinfunction "PB7_8") (pintype "unspecified"))
      (node (ref "X2") (pin "1") (pinfunction "OSC1_1") (pintype "input"))
    )
    (net (code "59") (name "Net-(U7-OSC1)") (class "Default")
      (node (ref "C15") (pin "1") (pinfunction "1_1") (pintype "unspecified"))
      (node (ref "U7") (pin "9") (pinfunction "OSC1_9") (pintype "unspecified"))
      (node (ref "X1") (pin "2") (pinfunction "OSC2_2") (pintype "input"))
    )
    (net (code "60") (name "Net-(U7-OSC2)") (class "Default")
      (node (ref "C11") (pin "1") (pinfunction "1_1") (pintype "unspecified"))
      (node (ref "U7") (pin "8") (pinfunction "OSC2_8") (pintype "output"))
      (node (ref "X1") (pin "1") (pinfunction "OSC1_1") (pintype "input"))
    )
    (net (code "61") (name "Net-(U7-RESET#)") (class "Default")
      (node (ref "R24") (pin "1") (pinfunction "1_1") (pintype "unspecified"))
      (node (ref "U7") (pin "19") (pinfunction "RESET#_19") (pintype "unspecified"))
    )
    (net (code "62") (name "Net-(U9-RS)") (class "Default")
      (node (ref "R21") (pin "2") (pinfunction "2_2") (pintype "unspecified"))
      (node (ref "U9") (pin "8") (pinfunction "RS_8") (pintype "unspecified"))
    )
    (net (code "63") (name "RX") (class "Default")
      (node (ref "U5") (pin "2") (pinfunction "R232_2") (pintype "unspecified"))
    )
    (net (code "64") (name "RXCAN1") (class "Default")
      (node (ref "U7") (pin "2") (pinfunction "RXCAN_2") (pintype "unspecified"))
      (node (ref "U9") (pin "4") (pinfunction "RXD_4") (pintype "unspecified"))
    )
    (net (code "65") (name "Reset") (class "Default")
      (node (ref "C14") (pin "1") (pinfunction "1_1") (pintype "unspecified"))
      (node (ref "ICSP2") (pin "2") (pinfunction "2_2") (pintype "input"))
      (node (ref "R18") (pin "1") (pinfunction "1_1") (pintype "unspecified"))
      (node (ref "SW2") (pin "2") (pinfunction "2_2") (pintype "input"))
      (node (ref "U6") (pin "29") (pinfunction "PC6_29") (pintype "unspecified"))
    )
    (net (code "66") (name "SCK1") (class "Default")
      (node (ref "ICSP2") (pin "6") (pinfunction "6_6") (pintype "input"))
      (node (ref "LED2") (pin "1") (pinfunction "A_1") (pintype "unspecified"))
      (node (ref "U6") (pin "17") (pinfunction "PB5_17") (pintype "unspecified"))
      (node (ref "U7") (pin "14") (pinfunction "SCK_14") (pintype "unspecified"))
    )
    (net (code "67") (name "SCL") (class "Default")
      (node (ref "U6") (pin "28") (pinfunction "PC5_28") (pintype "unspecified"))
    )
    (net (code "68") (name "SDA") (class "Default")
      (node (ref "U6") (pin "27") (pinfunction "PC4_27") (pintype "unspecified"))
    )
    (net (code "69") (name "SI1") (class "Default")
      (node (ref "ICSP2") (pin "3") (pinfunction "3_3") (pintype "input"))
      (node (ref "U6") (pin "15") (pinfunction "PB3_15") (pintype "unspecified"))
      (node (ref "U7") (pin "16") (pinfunction "SI_16") (pintype "unspecified"))
    )
    (net (code "70") (name "SO1") (class "Default")
      (node (ref "ICSP2") (pin "4") (pinfunction "4_4") (pintype "input"))
      (node (ref "U6") (pin "16") (pinfunction "PB4_16") (pintype "unspecified"))
      (node (ref "U7") (pin "17") (pinfunction "SO_17") (pintype "output"))
    )
    (net (code "71") (name "TX") (class "Default")
      (node (ref "U5") (pin "3") (pinfunction "RTS_3") (pintype "unspecified"))
    )
    (net (code "72") (name "TXCAN1") (class "Default")
      (node (ref "U7") (pin "1") (pinfunction "TXCAN_1") (pintype "output"))
      (node (ref "U9") (pin "1") (pinfunction "TXD_1") (pintype "unspecified"))
    )
    (net (code "73") (name "unconnected-(U1-27-Pad6)") (class "Default")
      (node (ref "U1") (pin "6") (pinfunction "27_6") (pintype "unspecified"))
    )
    (net (code "74") (name "unconnected-(U1-28-Pad5)") (class "Default")
      (node (ref "U1") (pin "5") (pinfunction "28_5") (pintype "unspecified"))
    )
    (net (code "75") (name "unconnected-(U1-29-Pad4)") (class "Default")
      (node (ref "U1") (pin "4") (pinfunction "29_4") (pintype "unspecified"))
    )
    (net (code "76") (name "unconnected-(U1-30-Pad3)") (class "Default")
      (node (ref "U1") (pin "3") (pinfunction "30_3") (pintype "unspecified"))
    )
    (net (code "77") (name "unconnected-(U1-31-Pad2)") (class "Default")
      (node (ref "U1") (pin "2") (pinfunction "31_2") (pintype "unspecified"))
    )
    (net (code "78") (name "unconnected-(U1-35-Pad62)") (class "Default")
      (node (ref "U1") (pin "62") (pinfunction "35_62") (pintype "unspecified"))
    )
    (net (code "79") (name "unconnected-(U1-37-Pad60)") (class "Default")
      (node (ref "U1") (pin "60") (pinfunction "37_60") (pintype "unspecified"))
    )
    (net (code "80") (name "unconnected-(U1-38-Pad59)") (class "Default")
      (node (ref "U1") (pin "59") (pinfunction "38_59") (pintype "unspecified"))
    )
    (net (code "81") (name "unconnected-(U2-Pad2)") (class "Default")
      (node (ref "U2") (pin "2") (pinfunction "2_2") (pintype "unspecified"))
    )
    (net (code "82") (name "unconnected-(U2-Pad3)") (class "Default")
      (node (ref "U2") (pin "3") (pinfunction "3_3") (pintype "unspecified"))
    )
    (net (code "83") (name "unconnected-(U2-Pad4)") (class "Default")
      (node (ref "U2") (pin "4") (pinfunction "4_4") (pintype "unspecified"))
    )
    (net (code "84") (name "unconnected-(U2-Pad5)") (class "Default")
      (node (ref "U2") (pin "5") (pinfunction "5_5") (pintype "unspecified"))
    )
    (net (code "85") (name "unconnected-(U2-Pad6)") (class "Default")
      (node (ref "U2") (pin "6") (pinfunction "6_6") (pintype "unspecified"))
    )
    (net (code "86") (name "unconnected-(U2-Pad59)") (class "Default")
      (node (ref "U2") (pin "59") (pinfunction "59_59") (pintype "unspecified"))
    )
    (net (code "87") (name "unconnected-(U2-Pad60)") (class "Default")
      (node (ref "U2") (pin "60") (pinfunction "60_60") (pintype "unspecified"))
    )
    (net (code "88") (name "unconnected-(U2-Pad62)") (class "Default")
      (node (ref "U2") (pin "62") (pinfunction "62_62") (pintype "unspecified"))
    )
    (net (code "89") (name "unconnected-(U2-Pad63)") (class "Default")
      (node (ref "U2") (pin "63") (pinfunction "63_63") (pintype "unspecified"))
    )
    (net (code "90") (name "unconnected-(U3-Pad2)") (class "Default")
      (node (ref "U3") (pin "2") (pinfunction "2_2") (pintype "unspecified"))
    )
    (net (code "91") (name "unconnected-(U3-Pad3)") (class "Default")
      (node (ref "U3") (pin "3") (pinfunction "3_3") (pintype "unspecified"))
    )
    (net (code "92") (name "unconnected-(U3-Pad4)") (class "Default")
      (node (ref "U3") (pin "4") (pinfunction "4_4") (pintype "unspecified"))
    )
    (net (code "93") (name "unconnected-(U3-Pad5)") (class "Default")
      (node (ref "U3") (pin "5") (pinfunction "5_5") (pintype "unspecified"))
    )
    (net (code "94") (name "unconnected-(U3-Pad6)") (class "Default")
      (node (ref "U3") (pin "6") (pinfunction "6_6") (pintype "unspecified"))
    )
    (net (code "95") (name "unconnected-(U3-Pad59)") (class "Default")
      (node (ref "U3") (pin "59") (pinfunction "59_59") (pintype "unspecified"))
    )
    (net (code "96") (name "unconnected-(U3-Pad60)") (class "Default")
      (node (ref "U3") (pin "60") (pinfunction "60_60") (pintype "unspecified"))
    )
    (net (code "97") (name "unconnected-(U3-Pad62)") (class "Default")
      (node (ref "U3") (pin "62") (pinfunction "62_62") (pintype "unspecified"))
    )
    (net (code "98") (name "unconnected-(U4-Pad2)") (class "Default")
      (node (ref "U4") (pin "2") (pinfunction "2_2") (pintype "unspecified"))
    )
    (net (code "99") (name "unconnected-(U4-Pad3)") (class "Default")
      (node (ref "U4") (pin "3") (pinfunction "3_3") (pintype "unspecified"))
    )
    (net (code "100") (name "unconnected-(U4-Pad4)") (class "Default")
      (node (ref "U4") (pin "4") (pinfunction "4_4") (pintype "unspecified"))
    )
    (net (code "101") (name "unconnected-(U4-Pad5)") (class "Default")
      (node (ref "U4") (pin "5") (pinfunction "5_5") (pintype "unspecified"))
    )
    (net (code "102") (name "unconnected-(U4-Pad6)") (class "Default")
      (node (ref "U4") (pin "6") (pinfunction "6_6") (pintype "unspecified"))
    )
    (net (code "103") (name "unconnected-(U4-Pad59)") (class "Default")
      (node (ref "U4") (pin "59") (pinfunction "59_59") (pintype "unspecified"))
    )
    (net (code "104") (name "unconnected-(U4-Pad60)") (class "Default")
      (node (ref "U4") (pin "60") (pinfunction "60_60") (pintype "unspecified"))
    )
    (net (code "105") (name "unconnected-(U4-Pad62)") (class "Default")
      (node (ref "U4") (pin "62") (pinfunction "62_62") (pintype "unspecified"))
    )
    (net (code "106") (name "unconnected-(U5-D+-Pad12)") (class "Default")
      (node (ref "U5") (pin "12") (pinfunction "D+_12") (pintype "unspecified"))
    )
    (net (code "107") (name "unconnected-(U5-D--Pad11)") (class "Default")
      (node (ref "U5") (pin "11") (pinfunction "D-_11") (pintype "unspecified"))
    )
    (net (code "108") (name "unconnected-(U5-RXD-Pad14)") (class "Default")
      (node (ref "U5") (pin "14") (pinfunction "RXD_14") (pintype "unspecified"))
    )
    (net (code "109") (name "unconnected-(U5-TXD-Pad15)") (class "Default")
      (node (ref "U5") (pin "15") (pinfunction "TXD_15") (pintype "unspecified"))
    )
    (net (code "110") (name "unconnected-(U5-XI-Pad10)") (class "Default")
      (node (ref "U5") (pin "10") (pinfunction "XI_10") (pintype "unspecified"))
    )
    (net (code "111") (name "unconnected-(U5-XO-Pad9)") (class "Default")
      (node (ref "U5") (pin "9") (pinfunction "XO_9") (pintype "unspecified"))
    )
    (net (code "112") (name "unconnected-(U6-ADC6-Pad19)") (class "Default")
      (node (ref "U6") (pin "19") (pinfunction "ADC6_19") (pintype "input"))
    )
    (net (code "113") (name "unconnected-(U6-ADC7-Pad22)") (class "Default")
      (node (ref "U6") (pin "22") (pinfunction "ADC7_22") (pintype "input"))
    )
    (net (code "114") (name "unconnected-(U7-CLKOUT{slash}SOF-Pad3)") (class "Default")
      (node (ref "U7") (pin "3") (pinfunction "CLKOUT/SOF_3") (pintype "output"))
    )
    (net (code "115") (name "unconnected-(U7-NC-Pad6)") (class "Default")
      (node (ref "U7") (pin "6") (pinfunction "NC_6") (pintype "unspecified"))
    )
    (net (code "116") (name "unconnected-(U7-NC-Pad15)") (class "Default")
      (node (ref "U7") (pin "15") (pinfunction "NC_15") (pintype "unspecified"))
    )
    (net (code "117") (name "unconnected-(U7-RX0BF#-Pad12)") (class "Default")
      (node (ref "U7") (pin "12") (pinfunction "RX0BF#_12") (pintype "output"))
    )
    (net (code "118") (name "unconnected-(U7-RX1BF#-Pad11)") (class "Default")
      (node (ref "U7") (pin "11") (pinfunction "RX1BF#_11") (pintype "output"))
    )
    (net (code "119") (name "unconnected-(U7-TX0RTS#-Pad4)") (class "Default")
      (node (ref "U7") (pin "4") (pinfunction "TX0RTS#_4") (pintype "unspecified"))
    )
    (net (code "120") (name "unconnected-(U7-TX1RTS#-Pad5)") (class "Default")
      (node (ref "U7") (pin "5") (pinfunction "TX1RTS#_5") (pintype "unspecified"))
    )
    (net (code "121") (name "unconnected-(U7-TX2RTS#-Pad7)") (class "Default")
      (node (ref "U7") (pin "7") (pinfunction "TX2RTS#_7") (pintype "unspecified"))
    )
    (net (code "122") (name "unconnected-(U9-VREF-Pad5)") (class "Default")
      (node (ref "U9") (pin "5") (pinfunction "VREF_5") (pintype "unspecified"))
    )
    (net (code "123") (name "unconnected-(USB3-ID-Pad4)") (class "Default")
      (node (ref "USB3") (pin "4") (pinfunction "ID_4") (pintype "input"))
    )
  )
)
